# conn_board_power.net
KiCad netlist of a schematic drawn in Altium Designer
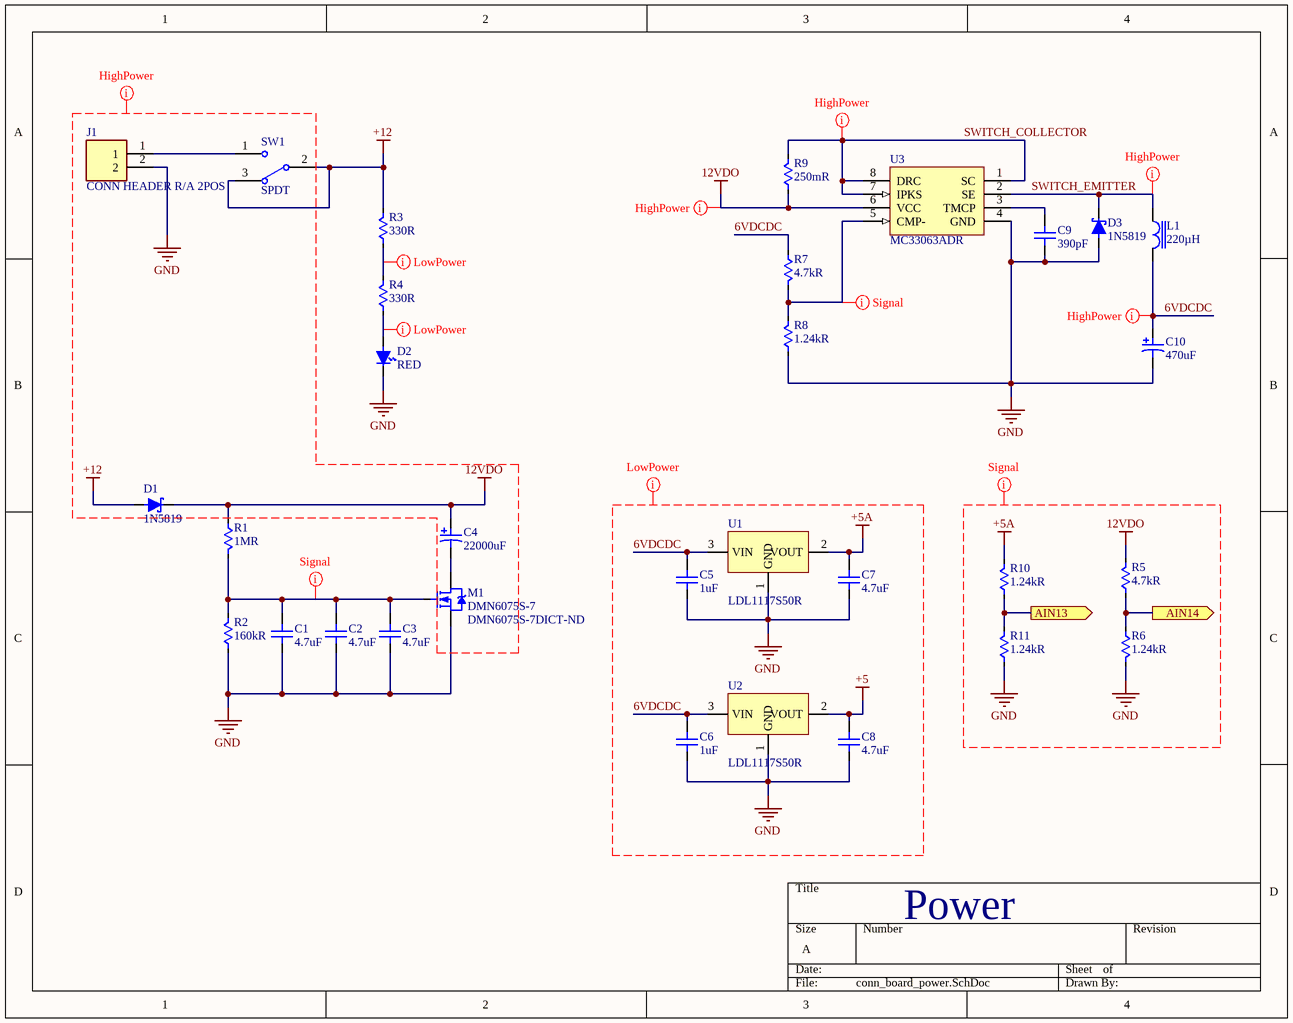
[diagram p0: conn_board_power.SchDoc]

(export (version "E")
  (design (tool "Eeschema 10.0.6"))
  (components
    (comp (ref "C1")
      (value "4.7uF")
      (footprint "CAP_0805")
      (fields
        (field (name "MANUFACTURER") "Samsung")
        (field (name "MANUFACTURER PART NUMBER") "CL21A475KAQNNNE")
        (field (name "TOLERANCE") "10%")
      )
      (libsource (lib "Schlib1") (part "CL21A475KAQNNNE"))
    )
    (comp (ref "C2")
      (value "4.7uF")
      (footprint "CAP_0805")
      (fields
        (field (name "MANUFACTURER") "Samsung")
        (field (name "MANUFACTURER PART NUMBER") "CL21A475KAQNNNE")
        (field (name "TOLERANCE") "10%")
      )
      (libsource (lib "Schlib1") (part "CL21A475KAQNNNE"))
    )
    (comp (ref "C3")
      (value "4.7uF")
      (footprint "CAP_0805")
      (fields
        (field (name "MANUFACTURER") "Samsung")
        (field (name "MANUFACTURER PART NUMBER") "CL21A475KAQNNNE")
        (field (name "TOLERANCE") "10%")
      )
      (libsource (lib "Schlib1") (part "CL21A475KAQNNNE"))
    )
    (comp (ref "C4")
      (value "22000uF")
      (footprint "UVR1C223MRD6_BENT_F")
      (description "Cap Aluminum 22000uF 16V 20% (25 X 40mm) Radial 12.5mm 4000mA 2000 hr 85°C Bulk")
      (fields
        (field (name "MANUFACTURER") "Nichicon")
        (field (name "MANUFACTURER PART NUMBER") "UVR1C223MRD6")
      )
      (libsource (lib "Schlib1") (part "UVR1C223MRD6"))
    )
    (comp (ref "C5")
      (value "1uF")
      (footprint "CAP_0805")
      (description "Cap Ceramic 1uF 16V Y5V -20% to 80% Pad SMD 0805 85C T/R")
      (fields
        (field (name "MANUFACTURER") "KEMET")
        (field (name "MANUFACTURER PART NUMBER") "C0805C105Z4VACTU")
      )
      (libsource (lib "Schlib1") (part "C0805C105Z4VACTU"))
    )
    (comp (ref "C6")
      (value "1uF")
      (footprint "CAP_0805")
      (description "Cap Ceramic 1uF 16V Y5V -20% to 80% Pad SMD 0805 85C T/R")
      (fields
        (field (name "MANUFACTURER") "KEMET")
        (field (name "MANUFACTURER PART NUMBER") "C0805C105Z4VACTU")
      )
      (libsource (lib "Schlib1") (part "C0805C105Z4VACTU"))
    )
    (comp (ref "C7")
      (value "4.7uF")
      (footprint "CAP_0805")
      (fields
        (field (name "MANUFACTURER") "Samsung")
        (field (name "MANUFACTURER PART NUMBER") "CL21A475KAQNNNE")
        (field (name "TOLERANCE") "10%")
      )
      (libsource (lib "Schlib1") (part "CL21A475KAQNNNE"))
    )
    (comp (ref "C8")
      (value "4.7uF")
      (footprint "CAP_0805")
      (fields
        (field (name "MANUFACTURER") "Samsung")
        (field (name "MANUFACTURER PART NUMBER") "CL21A475KAQNNNE")
        (field (name "TOLERANCE") "10%")
      )
      (libsource (lib "Schlib1") (part "CL21A475KAQNNNE"))
    )
    (comp (ref "C9")
      (value "390pF")
      (footprint "CAP_0805")
      (description "Cap Ceramic 390pF 50V C0G 5% SMD 0805 125C Paper T/R")
      (fields
        (field (name "MANUFACTURER") "Samsung")
        (field (name "MANUFACTURER PART NUMBER") "CL21C391JBANNNC")
      )
      (libsource (lib "Schlib1") (part "CL21C391JBANNNC"))
    )
    (comp (ref "C10")
      (value "470uF")
      (footprint "UUD1C471MNL1GS")
      (description "NICHICON   UUD1C471MNL1GS   CAP, ALU ELEC, 470UF, 16V, SMD")
      (fields
        (field (name "MANUFACTURER") "Nichicon")
        (field (name "MANUFACTURER PART NUMBER") "UUD1C471MNL1GS")
      )
      (libsource (lib "Schlib1") (part "UUD1C471MNL1GS"))
    )
    (comp (ref "D1")
      (value "1N5819")
      (footprint "SOD123")
      (description "DIODES INC. - 1N5819HW-7-F - DIODE, SCKY RECTI, 1A, 40V, SOD123")
      (fields (field (name "MANUFACTURER") "Diodes") (field (name "MANUFACTURER PART NUMBER") "1N5819HW-7-F"))
      (libsource (lib "Schlib1") (part "1N5819HW-7-F"))
    )
    (comp (ref "D2")
      (value "RED")
      (footprint "150080SS75000")
      (description "WURTH ELEKTRONIK   150080SS75000   LED, 0805, SUP RED, 60MCD, 630NM")
      (fields
        (field (name "MANUFACTURER") "Wurth Electronics")
        (field (name "MANUFACTURER PART NUMBER") "150080SS75000")
      )
      (libsource (lib "Schlib1") (part "150080SS75000"))
    )
    (comp (ref "D3")
      (value "1N5819")
      (footprint "SOD123")
      (description "DIODES INC. - 1N5819HW-7-F - DIODE, SCKY RECTI, 1A, 40V, SOD123")
      (fields (field (name "MANUFACTURER") "Diodes") (field (name "MANUFACTURER PART NUMBER") "1N5819HW-7-F"))
      (libsource (lib "Schlib1") (part "1N5819HW-7-F"))
    )
    (comp (ref "J1")
      (value "CONN HEADER R/A 2POS")
      (footprint "2 POS MOLEX")
      (fields (field (name "MANUFACTURER") "Molex") (field (name "MANUFACTURER PART NUMBER") "1724480002"))
      (libsource (lib "Schlib1") (part "1724480002"))
    )
    (comp (ref "L1")
      (value "220µH")
      (footprint "INDP125125X600N")
      (description "BOURNS   SRR1260-221K   INDUCTOR, SHIELDED, 220UH, 1.3A, SMD")
      (fields (field (name "MF") "Bourns - J.W. Miller") (field (name "MP") "SRR1260-221K"))
      (libsource (lib "Schlib1") (part "SRR1260-221K"))
    )
    (comp (ref "M1")
      (value "DMN6075S-7")
      (footprint "FP-SOT23-MFG")
      (description "MOSFET 60V N-Ch Enh FET 20Vgss 0.8W 600pF")
      (fields
        (field (name "MANUFACTURER") "Diodes Inc.")
        (field (name "OCTOPART") "https://octopart.com/dmn6075s-7-diodes+inc.-55697882")
        (field (name "SUPPLIER PART NUMBER 1") "DMN6075S-7DICT-ND")
      )
      (libsource (lib "Schlib1") (part "CMP-12801-000014-1"))
    )
    (comp (ref "R1")
      (value "1MR")
      (footprint "RES_0805_PANASONIC")
      (description "Res Thick Film 0805 1M Ohm 1% 1/8W ±100ppm/°C Molded SMD Punched Carrier T/R")
      (fields
        (field (name "MANUFACTURER") "Panasonic")
        (field (name "MANUFACTURER PART NUMBER") "ERJ-6ENF1004V")
      )
      (libsource (lib "Schlib1") (part "ERJ-6ENF1004V"))
    )
    (comp (ref "R2")
      (value "160kR")
      (footprint "RES_0805_PANASONIC")
      (description "Res Thick Film 0805 160K Ohm 1% 1/8W ±100ppm/°C Molded SMD Punched Carrier T/R")
      (fields
        (field (name "MANUFACTURER") "Panasonic")
        (field (name "MANUFACTURER PART NUMBER") "ERJ-6ENF1603V")
      )
      (libsource (lib "Schlib1") (part "ERJ-6ENF1603V"))
    )
    (comp (ref "R3")
      (value "330R")
      (footprint "RES_0805_PANASONIC")
      (description "Res Thin Film 0805 330 Ohm 0.5% 0.125W(1/8W) ±25ppm/C Molded SMD Automotive Punched T/R")
      (fields
        (field (name "MANUFACTURER") "Panasonic")
        (field (name "MANUFACTURER PART NUMBER") "ERA-6AED331V")
      )
      (libsource (lib "Schlib1") (part "ERA-6AED331V"))
    )
    (comp (ref "R4")
      (value "330R")
      (footprint "RES_0805_PANASONIC")
      (description "Res Thin Film 0805 330 Ohm 0.5% 0.125W(1/8W) ±25ppm/C Molded SMD Automotive Punched T/R")
      (fields
        (field (name "MANUFACTURER") "Panasonic")
        (field (name "MANUFACTURER PART NUMBER") "ERA-6AED331V")
      )
      (libsource (lib "Schlib1") (part "ERA-6AED331V"))
    )
    (comp (ref "R5")
      (value "4.7kR")
      (footprint "RES_0805_PANASONIC")
      (description "Res Thin Film 0805 4.7K Ohm 0.5% 0.125W(1/8W) ±25ppm/C Molded SMD Automotive Punched T/R")
      (fields
        (field (name "MANUFACTURER") "Panasonic")
        (field (name "MANUFACTURER PART NUMBER") "ERA-6AED472V")
      )
      (libsource (lib "Schlib1") (part "ERA-6AED472V"))
    )
    (comp (ref "R6")
      (value "1.24kR")
      (footprint "RES_0805_PANASONIC")
      (description "RES SMD 1.24K OHM 0.5% 1/4W 0805")
      (fields
        (field (name "MANUFACTURER") "Panasonic")
        (field (name "MANUFACTURER PART NUMBER") "ERJ-PB6D1241V")
      )
      (libsource (lib "Schlib1") (part "ERJ-PB6D1241V"))
    )
    (comp (ref "R7")
      (value "4.7kR")
      (footprint "RES_0805_PANASONIC")
      (description "Res Thin Film 0805 4.7K Ohm 0.5% 0.125W(1/8W) ±25ppm/C Molded SMD Automotive Punched T/R")
      (fields
        (field (name "MANUFACTURER") "Panasonic")
        (field (name "MANUFACTURER PART NUMBER") "ERA-6AED472V")
      )
      (libsource (lib "Schlib1") (part "ERA-6AED472V"))
    )
    (comp (ref "R8")
      (value "1.24kR")
      (footprint "RES_0805_PANASONIC")
      (description "RES SMD 1.24K OHM 0.5% 1/4W 0805")
      (fields
        (field (name "MANUFACTURER") "Panasonic")
        (field (name "MANUFACTURER PART NUMBER") "ERJ-PB6D1241V")
      )
      (libsource (lib "Schlib1") (part "ERJ-PB6D1241V"))
    )
    (comp (ref "R9")
      (value "250mR")
      (footprint "CSR1206FKR250")
      (description "Res Thick Film 1206 250m Ohm 1% 1/2W 100ppm/C Molded SMD Paper T/R")
      (fields
        (field (name "MANUFACTURER") "Stackpole Electronics")
        (field (name "MANUFACTURER PART NUMBER") "CSR1206FKR250")
      )
      (libsource (lib "Schlib1") (part "CSR1206FKR250"))
    )
    (comp (ref "R10")
      (value "1.24kR")
      (footprint "RES_0805_PANASONIC")
      (description "RES SMD 1.24K OHM 0.5% 1/4W 0805")
      (fields
        (field (name "MANUFACTURER") "Panasonic")
        (field (name "MANUFACTURER PART NUMBER") "ERJ-PB6D1241V")
      )
      (libsource (lib "Schlib1") (part "ERJ-PB6D1241V"))
    )
    (comp (ref "R11")
      (value "1.24kR")
      (footprint "RES_0805_PANASONIC")
      (description "RES SMD 1.24K OHM 0.5% 1/4W 0805")
      (fields
        (field (name "MANUFACTURER") "Panasonic")
        (field (name "MANUFACTURER PART NUMBER") "ERJ-PB6D1241V")
      )
      (libsource (lib "Schlib1") (part "ERJ-PB6D1241V"))
    )
    (comp (ref "SW1")
      (value "SPDT")
      (footprint "100SP1T2B4M6QE")
      (description "Switch Toggle ON None ON SPDT Round Lever PC Pins 5A 250VAC 28VDC PC Mount with Bracket")
      (fields
        (field (name "MANUFACTURER") "E-Switch")
        (field (name "MANUFACTURER PART NUMBER") "100SP1T2B4M6QE")
      )
      (libsource (lib "Schlib1") (part "100SP1T2B4M6QE"))
    )
    (comp (ref "U1")
      (value "LDL1117S50R")
      (footprint "SOT230P700X180-4N")
      (description "LDL1117 Series 1.2 A 5 V High PSRR LDO Linear Voltage Regulator - SOT-223")
      (fields (field (name "MANUFACTURER") "STMicroelectronics"))
      (libsource (lib "Schlib1") (part "LDL1117S50R"))
    )
    (comp (ref "U2")
      (value "LDL1117S50R")
      (footprint "SOT230P700X180-4N")
      (description "LDL1117 Series 1.2 A 5 V High PSRR LDO Linear Voltage Regulator - SOT-223")
      (fields (field (name "MANUFACTURER") "STMicroelectronics"))
      (libsource (lib "Schlib1") (part "LDL1117S50R"))
    )
    (comp (ref "U3")
      (value "MC33063ADR")
      (footprint "SOIC_8")
      (description "1.5-A peak boost/buck/inverting switching regulator 8-SOIC -40 to 85")
      (fields (field (name "MANUFACTURER") "Texas Instruments"))
      (libsource (lib "Schlib1") (part "MC33063ADR"))
    )
  )
  (nets
    (net (code "1") (name "+5") (class "Default")
      (node (ref "C8") (pin "2") (pinfunction "2_2") (pintype "passive"))
      (node (ref "U2") (pin "2") (pinfunction "VOUT_2") (pintype "passive"))
    )
    (net (code "2") (name "+5A") (class "Default")
      (node (ref "C7") (pin "2") (pinfunction "2_2") (pintype "passive"))
      (node (ref "R10") (pin "2") (pinfunction "2_2") (pintype "passive"))
      (node (ref "U1") (pin "2") (pinfunction "VOUT_2") (pintype "passive"))
    )
    (net (code "3") (name "+12") (class "Default")
      (node (ref "D1") (pin "2") (pinfunction "2_2") (pintype "passive"))
      (node (ref "R3") (pin "2") (pinfunction "2_2") (pintype "passive"))
      (node (ref "SW1") (pin "2") (pinfunction "2_2") (pintype "passive"))
      (node (ref "SW1") (pin "3") (pinfunction "3_3") (pintype "passive"))
    )
    (net (code "4") (name "/6VDCDC") (class "Default")
      (node (ref "C10") (pin "1") (pinfunction "1_1") (pintype "passive"))
      (node (ref "C5") (pin "2") (pinfunction "2_2") (pintype "passive"))
      (node (ref "C6") (pin "2") (pinfunction "2_2") (pintype "passive"))
      (node (ref "L1") (pin "1") (pinfunction "1_1") (pintype "passive"))
      (node (ref "R7") (pin "1") (pinfunction "1_1") (pintype "passive"))
      (node (ref "U1") (pin "3") (pinfunction "VIN_3") (pintype "passive"))
      (node (ref "U2") (pin "3") (pinfunction "VIN_3") (pintype "passive"))
    )
    (net (code "5") (name "/AIN13") (class "Default")
      (node (ref "R10") (pin "1") (pinfunction "1_1") (pintype "passive"))
      (node (ref "R11") (pin "2") (pinfunction "2_2") (pintype "passive"))
    )
    (net (code "6") (name "/AIN14") (class "Default")
      (node (ref "R5") (pin "1") (pinfunction "1_1") (pintype "passive"))
      (node (ref "R6") (pin "1") (pinfunction "1_1") (pintype "passive"))
    )
    (net (code "7") (name "/SWITCH_COLLECTOR") (class "Default")
      (node (ref "R9") (pin "2") (pinfunction "2_2") (pintype "passive"))
      (node (ref "U3") (pin "1") (pinfunction "SC_1") (pintype "open_collector"))
      (node (ref "U3") (pin "7") (pinfunction "IPKS_7") (pintype "input"))
      (node (ref "U3") (pin "8") (pinfunction "DRC_8") (pintype "open_collector"))
    )
    (net (code "8") (name "/SWITCH_EMITTER") (class "Default")
      (node (ref "D3") (pin "1") (pinfunction "1_1") (pintype "passive"))
      (node (ref "L1") (pin "2") (pinfunction "2_2") (pintype "passive"))
      (node (ref "U3") (pin "2") (pinfunction "SE_2") (pintype "open_emitter"))
    )
    (net (code "9") (name "12VDO") (class "Default")
      (node (ref "C4") (pin "1") (pinfunction "1_1") (pintype "passive"))
      (node (ref "D1") (pin "1") (pinfunction "1_1") (pintype "passive"))
      (node (ref "R1") (pin "1") (pinfunction "1_1") (pintype "passive"))
      (node (ref "R5") (pin "2") (pinfunction "2_2") (pintype "passive"))
      (node (ref "R9") (pin "1") (pinfunction "1_1") (pintype "passive"))
      (node (ref "U3") (pin "6") (pinfunction "VCC_6") (pintype "power_in"))
    )
    (net (code "10") (name "GND") (class "Default")
      (node (ref "C1") (pin "1") (pinfunction "1_1") (pintype "passive"))
      (node (ref "C10") (pin "2") (pinfunction "2_2") (pintype "passive"))
      (node (ref "C2") (pin "1") (pinfunction "1_1") (pintype "passive"))
      (node (ref "C3") (pin "1") (pinfunction "1_1") (pintype "passive"))
      (node (ref "C5") (pin "1") (pinfunction "1_1") (pintype "passive"))
      (node (ref "C6") (pin "1") (pinfunction "1_1") (pintype "passive"))
      (node (ref "C7") (pin "1") (pinfunction "1_1") (pintype "passive"))
      (node (ref "C8") (pin "1") (pinfunction "1_1") (pintype "passive"))
      (node (ref "C9") (pin "1") (pinfunction "1_1") (pintype "passive"))
      (node (ref "D2") (pin "1") (pinfunction "1_1") (pintype "passive"))
      (node (ref "D3") (pin "2") (pinfunction "2_2") (pintype "passive"))
      (node (ref "J1") (pin "2") (pinfunction "2_2") (pintype "passive"))
      (node (ref "M1") (pin "S") (pinfunction "S_S") (pintype "passive"))
      (node (ref "R11") (pin "1") (pinfunction "1_1") (pintype "passive"))
      (node (ref "R2") (pin "1") (pinfunction "1_1") (pintype "passive"))
      (node (ref "R6") (pin "2") (pinfunction "2_2") (pintype "passive"))
      (node (ref "R8") (pin "1") (pinfunction "1_1") (pintype "passive"))
      (node (ref "U1") (pin "1") (pinfunction "GND_1") (pintype "passive"))
      (node (ref "U2") (pin "1") (pinfunction "GND_1") (pintype "passive"))
      (node (ref "U3") (pin "4") (pinfunction "GND_4") (pintype "power_in"))
    )
    (net (code "11") (name "Net-(C1-Pad2)") (class "Default")
      (node (ref "C1") (pin "2") (pinfunction "2_2") (pintype "passive"))
      (node (ref "C2") (pin "2") (pinfunction "2_2") (pintype "passive"))
      (node (ref "C3") (pin "2") (pinfunction "2_2") (pintype "passive"))
      (node (ref "M1") (pin "G") (pinfunction "G_G") (pintype "passive"))
      (node (ref "R1") (pin "2") (pinfunction "2_2") (pintype "passive"))
      (node (ref "R2") (pin "2") (pinfunction "2_2") (pintype "passive"))
    )
    (net (code "12") (name "Net-(C4-Pad2)") (class "Default")
      (node (ref "C4") (pin "2") (pinfunction "2_2") (pintype "passive"))
      (node (ref "M1") (pin "D") (pinfunction "D_D") (pintype "passive"))
    )
    (net (code "13") (name "Net-(D2-Pad2)") (class "Default")
      (node (ref "D2") (pin "2") (pinfunction "2_2") (pintype "passive"))
      (node (ref "R4") (pin "1") (pinfunction "1_1") (pintype "passive"))
    )
    (net (code "14") (name "Net-(J1-Pad1)") (class "Default")
      (node (ref "J1") (pin "1") (pinfunction "1_1") (pintype "passive"))
      (node (ref "SW1") (pin "1") (pinfunction "1_1") (pintype "passive"))
    )
    (net (code "15") (name "Net-(R3-Pad1)") (class "Default")
      (node (ref "R3") (pin "1") (pinfunction "1_1") (pintype "passive"))
      (node (ref "R4") (pin "2") (pinfunction "2_2") (pintype "passive"))
    )
    (net (code "16") (name "Net-(U3-CMP-)") (class "Default")
      (node (ref "R7") (pin "2") (pinfunction "2_2") (pintype "passive"))
      (node (ref "R8") (pin "2") (pinfunction "2_2") (pintype "passive"))
      (node (ref "U3") (pin "5") (pinfunction "CMP-_5") (pintype "input"))
    )
    (net (code "17") (name "Net-(U3-TMCP)") (class "Default")
      (node (ref "C9") (pin "2") (pinfunction "2_2") (pintype "passive"))
      (node (ref "U3") (pin "3") (pinfunction "TMCP_3") (pintype "open_emitter"))
    )
  )
)
